# ADC_1_Board.net
KiCad netlist of a schematic drawn in Altium Designer
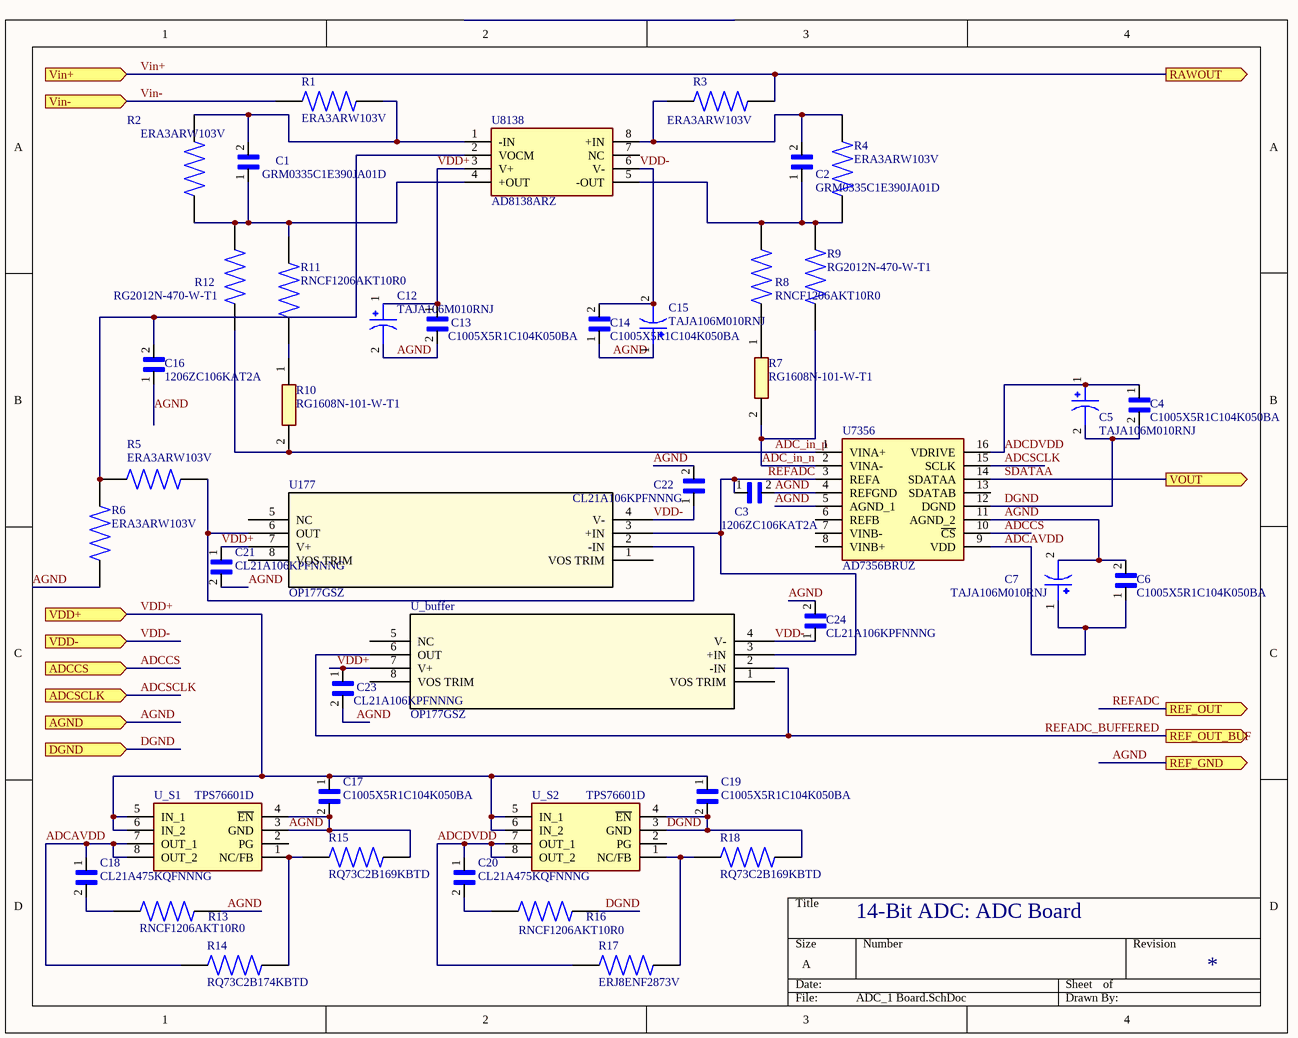
[diagram p0: ADC_1 Board.SchDoc]

(export (version "E")
  (design (tool "Eeschema 10.0.6"))
  (components
    (comp (ref "C1")
      (value "GRM0335C1E390JA01D")
      (footprint "CAPC0603X33N")
      (description "SMD Capacitor C0G(EIA) with Capacitance: 39pF Tol. 5%. Rated Voltage: 25Vdc")
      (libsource (lib "GRM0335C1E390JA01D") (part "GRM0335C1E390JA01D"))
    )
    (comp (ref "C2")
      (value "GRM0335C1E390JA01D")
      (footprint "CAPC0603X33N")
      (description "SMD Capacitor C0G(EIA) with Capacitance: 39pF Tol. 5%. Rated Voltage: 25Vdc")
      (libsource (lib "GRM0335C1E390JA01D") (part "GRM0335C1E390JA01D"))
    )
    (comp (ref "C3")
      (value "1206ZC106KAT2A")
      (footprint "CAPC3216X178N")
      (description "10ÂµF Â±10% 10V Ceramic Capacitor X7R 1206 (3216 Metric)")
      (fields (field (name "MF") "AVX"))
      (libsource (lib "1206ZC106KAT2A") (part "1206ZC106KAT2A"))
    )
    (comp (ref "C4")
      (value "C1005X5R1C104K050BA")
      (footprint "CAPC1005X55N")
      (description "CERAMIC CAPACITOR, 0.1UF, 16V, X5R, 10%, 0402")
      (libsource (lib "") (part "C1005X5R1C104K050BA_1"))
    )
    (comp (ref "C5")
      (value "TAJA106M010RNJ")
      (footprint "CAPMP3216X180N")
      (description "10ÂµF Molded Tantalum Capacitors 10V 1206 (3216 Metric) 3Ohm")
      (fields (field (name "MF") "AVX"))
      (libsource (lib "") (part "TAJA106M010RNJ_1"))
    )
    (comp (ref "C6")
      (value "C1005X5R1C104K050BA")
      (footprint "CAPC1005X55N")
      (description "CERAMIC CAPACITOR, 0.1UF, 16V, X5R, 10%, 0402")
      (libsource (lib "C1005X5R1C104K050BA") (part "C1005X5R1C104K050BA"))
    )
    (comp (ref "C7")
      (value "TAJA106M010RNJ")
      (footprint "CAPMP3216X180N")
      (description "10ÂµF Molded Tantalum Capacitors 10V 1206 (3216 Metric) 3Ohm")
      (fields (field (name "MF") "AVX"))
      (libsource (lib "TAJA106M010RNJ") (part "TAJA106M010RNJ"))
    )
    (comp (ref "C12")
      (value "TAJA106M010RNJ")
      (footprint "CAPMP3216X180N")
      (description "10ÂµF Molded Tantalum Capacitors 10V 1206 (3216 Metric) 3Ohm")
      (fields (field (name "MF") "AVX"))
      (libsource (lib "") (part "TAJA106M010RNJ_1"))
    )
    (comp (ref "C13")
      (value "C1005X5R1C104K050BA")
      (footprint "CAPC1005X55N")
      (description "CERAMIC CAPACITOR, 0.1UF, 16V, X5R, 10%, 0402")
      (libsource (lib "") (part "C1005X5R1C104K050BA_1"))
    )
    (comp (ref "C14")
      (value "C1005X5R1C104K050BA")
      (footprint "CAPC1005X55N")
      (description "CERAMIC CAPACITOR, 0.1UF, 16V, X5R, 10%, 0402")
      (libsource (lib "C1005X5R1C104K050BA") (part "C1005X5R1C104K050BA"))
    )
    (comp (ref "C15")
      (value "TAJA106M010RNJ")
      (footprint "CAPMP3216X180N")
      (description "10ÂµF Molded Tantalum Capacitors 10V 1206 (3216 Metric) 3Ohm")
      (fields (field (name "MF") "AVX"))
      (libsource (lib "TAJA106M010RNJ") (part "TAJA106M010RNJ"))
    )
    (comp (ref "C16")
      (value "1206ZC106KAT2A")
      (footprint "CAPC3216X178N")
      (description "10ÂµF Â±10% 10V Ceramic Capacitor X7R 1206 (3216 Metric)")
      (fields (field (name "MF") "AVX"))
      (libsource (lib "") (part "1206ZC106KAT2A_1"))
    )
    (comp (ref "C17")
      (value "C1005X5R1C104K050BA")
      (footprint "CAPC1005X55N")
      (description "CERAMIC CAPACITOR, 0.1UF, 16V, X5R, 10%, 0402")
      (libsource (lib "") (part "C1005X5R1C104K050BA_1"))
    )
    (comp (ref "C18")
      (value "CL21A475KQFNNNG")
      (footprint "CAPC2012X135N")
      (description "4.7U 6.3V K0805 X5R")
      (libsource (lib "CL21A475KQFNNNG") (part "CL21A475KQFNNNG"))
    )
    (comp (ref "C19")
      (value "C1005X5R1C104K050BA")
      (footprint "CAPC1005X55N")
      (description "CERAMIC CAPACITOR, 0.1UF, 16V, X5R, 10%, 0402")
      (libsource (lib "") (part "C1005X5R1C104K050BA_1"))
    )
    (comp (ref "C20")
      (value "CL21A475KQFNNNG")
      (footprint "CAPC2012X135N")
      (description "4.7U 6.3V K0805 X5R")
      (libsource (lib "CL21A475KQFNNNG") (part "CL21A475KQFNNNG"))
    )
    (comp (ref "C21")
      (value "CL21A106KPFNNNG")
      (footprint "CAPC2012X135N")
      (description "10ÂµF Â±10% 10V Ceramic Capacitor X5R 0805 (2012 Metric)")
      (fields
        (field (name "MF") "Samsung Electro-Mechanics")
        (field (name "DIGI-KEY_PART_NUMBER") "1276-6456-1-ND")
      )
      (libsource (lib "CL21A106KPFNNNG") (part "CL21A106KPFNNNG"))
    )
    (comp (ref "C22")
      (value "CL21A106KPFNNNG")
      (footprint "CAPC2012X135N")
      (description "10ÂµF Â±10% 10V Ceramic Capacitor X5R 0805 (2012 Metric)")
      (fields
        (field (name "MF") "Samsung Electro-Mechanics")
        (field (name "DIGI-KEY_PART_NUMBER") "1276-6456-1-ND")
      )
      (libsource (lib "") (part "CL21A106KPFNNNG_1"))
    )
    (comp (ref "C23")
      (value "CL21A106KPFNNNG")
      (footprint "CAPC2012X135N")
      (description "10ÂµF Â±10% 10V Ceramic Capacitor X5R 0805 (2012 Metric)")
      (fields
        (field (name "MF") "Samsung Electro-Mechanics")
        (field (name "DIGI-KEY_PART_NUMBER") "1276-6456-1-ND")
      )
      (libsource (lib "CL21A106KPFNNNG") (part "CL21A106KPFNNNG"))
    )
    (comp (ref "C24")
      (value "CL21A106KPFNNNG")
      (footprint "CAPC2012X135N")
      (description "10ÂµF Â±10% 10V Ceramic Capacitor X5R 0805 (2012 Metric)")
      (fields
        (field (name "MF") "Samsung Electro-Mechanics")
        (field (name "DIGI-KEY_PART_NUMBER") "1276-6456-1-ND")
      )
      (libsource (lib "") (part "CL21A106KPFNNNG_1"))
    )
    (comp (ref "R1")
      (value "ERA3ARW103V")
      (footprint "RES_ERA3ARW103V")
      (libsource (lib "ERA3ARW103V") (part "ERA3ARW103V"))
    )
    (comp (ref "R2")
      (value "ERA3ARW103V")
      (footprint "RES_ERA3ARW103V")
      (libsource (lib "ERA3ARW103V") (part "ERA3ARW103V"))
    )
    (comp (ref "R3")
      (value "ERA3ARW103V")
      (footprint "RES_ERA3ARW103V")
      (libsource (lib "ERA3ARW103V") (part "ERA3ARW103V"))
    )
    (comp (ref "R4")
      (value "ERA3ARW103V")
      (footprint "RES_ERA3ARW103V")
      (libsource (lib "ERA3ARW103V") (part "ERA3ARW103V"))
    )
    (comp (ref "R5")
      (value "ERA3ARW103V")
      (footprint "RES_ERA3ARW103V")
      (libsource (lib "ERA3ARW103V") (part "ERA3ARW103V"))
    )
    (comp (ref "R6")
      (value "ERA3ARW103V")
      (footprint "RES_ERA3ARW103V")
      (libsource (lib "ERA3ARW103V") (part "ERA3ARW103V"))
    )
    (comp (ref "R7")
      (value "RG1608N-101-W-T1")
      (footprint "SamacSys:RESC1608X50N")
      (description "Resistor")
      (libsource (lib "*") (part "RG1608N-101-W-T1"))
    )
    (comp (ref "R8")
      (value "RNCF1206AKT10R0")
      (footprint "RESC3015X65N")
      (libsource (lib "RNCF1206AKT10R0") (part "RNCF1206AKT10R0"))
    )
    (comp (ref "R9")
      (value "RG2012N-470-W-T1")
      (footprint "RESC2012X50N")
      (libsource (lib "RG2012N-470-W-T1") (part "RG2012N-470-W-T1"))
    )
    (comp (ref "R10")
      (value "RG1608N-101-W-T1")
      (footprint "SamacSys:RESC1608X50N")
      (description "Resistor")
      (libsource (lib "*") (part "RG1608N-101-W-T1"))
    )
    (comp (ref "R11")
      (value "RNCF1206AKT10R0")
      (footprint "RESC3015X65N")
      (libsource (lib "RNCF1206AKT10R0") (part "RNCF1206AKT10R0"))
    )
    (comp (ref "R12")
      (value "RG2012N-470-W-T1")
      (footprint "RESC2012X50N")
      (libsource (lib "RG2012N-470-W-T1") (part "RG2012N-470-W-T1"))
    )
    (comp (ref "R13")
      (value "RNCF1206AKT10R0")
      (footprint "RESC3015X65N")
      (libsource (lib "RNCF1206AKT10R0") (part "RNCF1206AKT10R0"))
    )
    (comp (ref "R14")
      (value "RQ73C2B174KBTD")
      (footprint "RESC3116X75N")
      (libsource (lib "RQ73C2B174KBTD") (part "RQ73C2B174KBTD"))
    )
    (comp (ref "R15")
      (value "RQ73C2B169KBTD")
      (footprint "RESC3116X75N")
      (libsource (lib "RQ73C2B169KBTD") (part "RQ73C2B169KBTD"))
    )
    (comp (ref "R16")
      (value "RNCF1206AKT10R0")
      (footprint "RESC3015X65N")
      (libsource (lib "RNCF1206AKT10R0") (part "RNCF1206AKT10R0"))
    )
    (comp (ref "R17")
      (value "ERJ8ENF2873V")
      (footprint "RES_ERJ8ENF2873V")
      (libsource (lib "ERJ8ENF2873V") (part "ERJ8ENF2873V"))
    )
    (comp (ref "R18")
      (value "RQ73C2B169KBTD")
      (footprint "RESC3116X75N")
      (libsource (lib "RQ73C2B169KBTD") (part "RQ73C2B169KBTD"))
    )
    (comp (ref "U177")
      (value "OP177GSZ")
      (footprint "R_8_ADI")
      (description "No Description Available")
      (fields (field (name "COPYRIGHT") "Copyright (C) 2021 Accelerated Designs. All rights reserved"))
      (libsource (lib "OP177GSZ") (part "OP177GSZ"))
    )
    (comp (ref "U7356")
      (value "AD7356BRUZ")
      (footprint "SamacSys:SOP65P640X120-16N")
      (description "Integrated Circuit")
      (libsource (lib "*") (part "AD7356BRUZ"))
    )
    (comp (ref "U8138")
      (value "AD8138ARZ")
      (footprint "SamacSys:SOIC127P600X175-8N")
      (description "Integrated Circuit")
      (fields (field (name "MOUSER2 PART NUMBER") "584-AD8138ARZ"))
      (libsource (lib "*") (part "AD8138ARZ"))
    )
    (comp (ref "U_buffer")
      (value "OP177GSZ")
      (footprint "R_8_ADI")
      (description "No Description Available")
      (fields (field (name "COPYRIGHT") "Copyright (C) 2021 Accelerated Designs. All rights reserved"))
      (libsource (lib "OP177GSZ") (part "OP177GSZ"))
    )
    (comp (ref "U_S1")
      (value "TPS76601D")
      (footprint "SamacSys:SOIC127P600X175-8N")
      (description "Integrated Circuit")
      (libsource (lib "*") (part "TPS76601D"))
    )
    (comp (ref "U_S2")
      (value "TPS76601D")
      (footprint "SamacSys:SOIC127P600X175-8N")
      (description "Integrated Circuit")
      (libsource (lib "*") (part "TPS76601D"))
    )
  )
  (nets
    (net (code "1") (name "/ADCAVDD") (class "Default")
      (node (ref "C18") (pin "1") (pinfunction "1_1") (pintype "passive"))
      (node (ref "C6") (pin "1") (pinfunction "1_1") (pintype "passive"))
      (node (ref "C7") (pin "1") (pinfunction "1_1") (pintype "passive"))
      (node (ref "R14") (pin "1") (pinfunction "1_1") (pintype "passive"))
      (node (ref "U7356") (pin "9") (pinfunction "VDD_9") (pintype "passive"))
      (node (ref "U_S1") (pin "7") (pinfunction "OUT_1_7") (pintype "passive"))
      (node (ref "U_S1") (pin "8") (pinfunction "OUT_2_8") (pintype "passive"))
    )
    (net (code "2") (name "/ADCCS") (class "Default")
      (node (ref "U7356") (pin "10") (pinfunction "~{CS}_10") (pintype "passive"))
    )
    (net (code "3") (name "/ADCDVDD") (class "Default")
      (node (ref "C20") (pin "1") (pinfunction "1_1") (pintype "passive"))
      (node (ref "C4") (pin "1") (pinfunction "1_1") (pintype "passive"))
      (node (ref "C5") (pin "1") (pinfunction "1_1") (pintype "passive"))
      (node (ref "R17") (pin "1") (pinfunction "1_1") (pintype "passive"))
      (node (ref "U7356") (pin "16") (pinfunction "VDRIVE_16") (pintype "passive"))
      (node (ref "U_S2") (pin "7") (pinfunction "OUT_1_7") (pintype "passive"))
      (node (ref "U_S2") (pin "8") (pinfunction "OUT_2_8") (pintype "passive"))
    )
    (net (code "4") (name "/ADCSCLK") (class "Default")
      (node (ref "U7356") (pin "15") (pinfunction "SCLK_15") (pintype "passive"))
    )
    (net (code "5") (name "/ADC_in_n") (class "Default")
      (node (ref "R7") (pin "2") (pinfunction "2_2") (pintype "passive"))
      (node (ref "R9") (pin "2") (pinfunction "2_2") (pintype "passive"))
      (node (ref "U7356") (pin "2") (pinfunction "VINA-_2") (pintype "passive"))
    )
    (net (code "6") (name "/ADC_in_p") (class "Default")
      (node (ref "R10") (pin "2") (pinfunction "2_2") (pintype "passive"))
      (node (ref "R12") (pin "2") (pinfunction "2_2") (pintype "passive"))
      (node (ref "U7356") (pin "1") (pinfunction "VINA+_1") (pintype "passive"))
    )
    (net (code "7") (name "/AGND") (class "Default")
      (node (ref "C12") (pin "2") (pinfunction "2_2") (pintype "passive"))
      (node (ref "C13") (pin "2") (pinfunction "2_2") (pintype "passive"))
      (node (ref "C14") (pin "1") (pinfunction "1_1") (pintype "passive"))
      (node (ref "C15") (pin "1") (pinfunction "1_1") (pintype "passive"))
      (node (ref "C16") (pin "1") (pinfunction "1_1") (pintype "passive"))
      (node (ref "C17") (pin "2") (pinfunction "2_2") (pintype "passive"))
      (node (ref "C21") (pin "2") (pinfunction "2_2") (pintype "passive"))
      (node (ref "C22") (pin "2") (pinfunction "2_2") (pintype "passive"))
      (node (ref "C23") (pin "2") (pinfunction "2_2") (pintype "passive"))
      (node (ref "C24") (pin "2") (pinfunction "2_2") (pintype "passive"))
      (node (ref "C3") (pin "2") (pinfunction "2_2") (pintype "passive"))
      (node (ref "C6") (pin "2") (pinfunction "2_2") (pintype "passive"))
      (node (ref "C7") (pin "2") (pinfunction "2_2") (pintype "passive"))
      (node (ref "R13") (pin "1") (pinfunction "1_1") (pintype "passive"))
      (node (ref "R15") (pin "2") (pinfunction "2_2") (pintype "passive"))
      (node (ref "R6") (pin "2") (pinfunction "2_2") (pintype "passive"))
      (node (ref "U7356") (pin "11") (pinfunction "AGND_2_11") (pintype "passive"))
      (node (ref "U7356") (pin "4") (pinfunction "REFGND_4") (pintype "passive"))
      (node (ref "U7356") (pin "5") (pinfunction "AGND_1_5") (pintype "passive"))
      (node (ref "U_S1") (pin "3") (pinfunction "GND_3") (pintype "passive"))
      (node (ref "U_S1") (pin "4") (pinfunction "~{EN}_4") (pintype "passive"))
    )
    (net (code "8") (name "/DGND") (class "Default")
      (node (ref "C19") (pin "2") (pinfunction "2_2") (pintype "passive"))
      (node (ref "C4") (pin "2") (pinfunction "2_2") (pintype "passive"))
      (node (ref "C5") (pin "2") (pinfunction "2_2") (pintype "passive"))
      (node (ref "R16") (pin "1") (pinfunction "1_1") (pintype "passive"))
      (node (ref "R18") (pin "2") (pinfunction "2_2") (pintype "passive"))
      (node (ref "U7356") (pin "12") (pinfunction "DGND_12") (pintype "passive"))
      (node (ref "U_S2") (pin "3") (pinfunction "GND_3") (pintype "passive"))
      (node (ref "U_S2") (pin "4") (pinfunction "~{EN}_4") (pintype "passive"))
    )
    (net (code "9") (name "/REFADC") (class "Default")
      (node (ref "C3") (pin "1") (pinfunction "1_1") (pintype "passive"))
      (node (ref "U177") (pin "3") (pinfunction "+IN_3") (pintype "passive"))
      (node (ref "U7356") (pin "3") (pinfunction "REFA_3") (pintype "passive"))
      (node (ref "U_buffer") (pin "3") (pinfunction "+IN_3") (pintype "passive"))
    )
    (net (code "10") (name "/REFADC_BUFFERED") (class "Default")
      (node (ref "U_buffer") (pin "2") (pinfunction "-IN_2") (pintype "passive"))
      (node (ref "U_buffer") (pin "6") (pinfunction "OUT_6") (pintype "passive"))
    )
    (net (code "11") (name "/SDATAA") (class "Default")
      (node (ref "U7356") (pin "14") (pinfunction "SDATAA_14") (pintype "passive"))
    )
    (net (code "12") (name "/VDD+") (class "Default")
      (node (ref "C12") (pin "1") (pinfunction "1_1") (pintype "passive"))
      (node (ref "C13") (pin "1") (pinfunction "1_1") (pintype "passive"))
      (node (ref "C17") (pin "1") (pinfunction "1_1") (pintype "passive"))
      (node (ref "C19") (pin "1") (pinfunction "1_1") (pintype "passive"))
      (node (ref "C21") (pin "1") (pinfunction "1_1") (pintype "passive"))
      (node (ref "C23") (pin "1") (pinfunction "1_1") (pintype "passive"))
      (node (ref "U177") (pin "7") (pinfunction "V+_7") (pintype "power_in"))
      (node (ref "U8138") (pin "3") (pinfunction "V+_3") (pintype "passive"))
      (node (ref "U_S1") (pin "5") (pinfunction "IN_1_5") (pintype "passive"))
      (node (ref "U_S1") (pin "6") (pinfunction "IN_2_6") (pintype "passive"))
      (node (ref "U_S2") (pin "5") (pinfunction "IN_1_5") (pintype "passive"))
      (node (ref "U_S2") (pin "6") (pinfunction "IN_2_6") (pintype "passive"))
      (node (ref "U_buffer") (pin "7") (pinfunction "V+_7") (pintype "power_in"))
    )
    (net (code "13") (name "/VDD-") (class "Default")
      (node (ref "C14") (pin "2") (pinfunction "2_2") (pintype "passive"))
      (node (ref "C15") (pin "2") (pinfunction "2_2") (pintype "passive"))
      (node (ref "C22") (pin "1") (pinfunction "1_1") (pintype "passive"))
      (node (ref "C24") (pin "1") (pinfunction "1_1") (pintype "passive"))
      (node (ref "U177") (pin "4") (pinfunction "V-_4") (pintype "power_in"))
      (node (ref "U8138") (pin "6") (pinfunction "V-_6") (pintype "passive"))
      (node (ref "U_buffer") (pin "4") (pinfunction "V-_4") (pintype "power_in"))
    )
    (net (code "14") (name "/Vin+") (class "Default")
      (node (ref "R3") (pin "1") (pinfunction "1_1") (pintype "passive"))
    )
    (net (code "15") (name "/Vin-") (class "Default")
      (node (ref "R1") (pin "2") (pinfunction "2_2") (pintype "passive"))
    )
    (net (code "16") (name "Net-(C18-Pad2)") (class "Default")
      (node (ref "C18") (pin "2") (pinfunction "2_2") (pintype "passive"))
      (node (ref "R13") (pin "2") (pinfunction "2_2") (pintype "passive"))
    )
    (net (code "17") (name "Net-(C20-Pad2)") (class "Default")
      (node (ref "C20") (pin "2") (pinfunction "2_2") (pintype "passive"))
      (node (ref "R16") (pin "2") (pinfunction "2_2") (pintype "passive"))
    )
    (net (code "18") (name "Net-(R7-Pad1)") (class "Default")
      (node (ref "R7") (pin "1") (pinfunction "1_1") (pintype "passive"))
      (node (ref "R8") (pin "1") (pinfunction "1_1") (pintype "passive"))
    )
    (net (code "19") (name "Net-(R10-Pad1)") (class "Default")
      (node (ref "R10") (pin "1") (pinfunction "1_1") (pintype "passive"))
      (node (ref "R11") (pin "2") (pinfunction "2_2") (pintype "passive"))
    )
    (net (code "20") (name "Net-(U177--IN)") (class "Default")
      (node (ref "R5") (pin "2") (pinfunction "2_2") (pintype "passive"))
      (node (ref "U177") (pin "2") (pinfunction "-IN_2") (pintype "passive"))
      (node (ref "U177") (pin "6") (pinfunction "OUT_6") (pintype "passive"))
    )
    (net (code "21") (name "Net-(U8138-+IN)") (class "Default")
      (node (ref "C2") (pin "2") (pinfunction "2_2") (pintype "passive"))
      (node (ref "R3") (pin "2") (pinfunction "2_2") (pintype "passive"))
      (node (ref "R4") (pin "1") (pinfunction "1_1") (pintype "passive"))
      (node (ref "U8138") (pin "8") (pinfunction "+IN_8") (pintype "passive"))
    )
    (net (code "22") (name "Net-(U8138-+OUT)") (class "Default")
      (node (ref "C1") (pin "1") (pinfunction "1_1") (pintype "passive"))
      (node (ref "R11") (pin "1") (pinfunction "1_1") (pintype "passive"))
      (node (ref "R12") (pin "1") (pinfunction "1_1") (pintype "passive"))
      (node (ref "R2") (pin "2") (pinfunction "2_2") (pintype "passive"))
      (node (ref "U8138") (pin "4") (pinfunction "+OUT_4") (pintype "passive"))
    )
    (net (code "23") (name "Net-(U8138--IN)") (class "Default")
      (node (ref "C1") (pin "2") (pinfunction "2_2") (pintype "passive"))
      (node (ref "R1") (pin "1") (pinfunction "1_1") (pintype "passive"))
      (node (ref "R2") (pin "1") (pinfunction "1_1") (pintype "passive"))
      (node (ref "U8138") (pin "1") (pinfunction "-IN_1") (pintype "passive"))
    )
    (net (code "24") (name "Net-(U8138--OUT)") (class "Default")
      (node (ref "C2") (pin "1") (pinfunction "1_1") (pintype "passive"))
      (node (ref "R4") (pin "2") (pinfunction "2_2") (pintype "passive"))
      (node (ref "R8") (pin "2") (pinfunction "2_2") (pintype "passive"))
      (node (ref "R9") (pin "1") (pinfunction "1_1") (pintype "passive"))
      (node (ref "U8138") (pin "5") (pinfunction "-OUT_5") (pintype "passive"))
    )
    (net (code "25") (name "Net-(U8138-VOCM)") (class "Default")
      (node (ref "C16") (pin "2") (pinfunction "2_2") (pintype "passive"))
      (node (ref "R5") (pin "1") (pinfunction "1_1") (pintype "passive"))
      (node (ref "R6") (pin "1") (pinfunction "1_1") (pintype "passive"))
      (node (ref "U8138") (pin "2") (pinfunction "VOCM_2") (pintype "passive"))
    )
    (net (code "26") (name "Net-(U_S1-NC{slash}FB)") (class "Default")
      (node (ref "R14") (pin "2") (pinfunction "2_2") (pintype "passive"))
      (node (ref "R15") (pin "1") (pinfunction "1_1") (pintype "passive"))
      (node (ref "U_S1") (pin "1") (pinfunction "NC/FB_1") (pintype "passive"))
    )
    (net (code "27") (name "Net-(U_S2-NC{slash}FB)") (class "Default")
      (node (ref "R17") (pin "2") (pinfunction "2_2") (pintype "passive"))
      (node (ref "R18") (pin "1") (pinfunction "1_1") (pintype "passive"))
      (node (ref "U_S2") (pin "1") (pinfunction "NC/FB_1") (pintype "passive"))
    )
    (net (code "28") (name "unconnected-(U177-NC-Pad5)") (class "Default")
      (node (ref "U177") (pin "5") (pinfunction "NC_5") (pintype "passive"))
    )
    (net (code "29") (name "unconnected-(U177-VOS_TRIM-Pad1)") (class "Default")
      (node (ref "U177") (pin "1") (pinfunction "VOS_TRIM_1") (pintype "passive"))
    )
    (net (code "30") (name "unconnected-(U177-VOS_TRIM-Pad8)") (class "Default")
      (node (ref "U177") (pin "8") (pinfunction "VOS_TRIM_8") (pintype "power_in"))
    )
    (net (code "31") (name "unconnected-(U7356-REFB-Pad6)") (class "Default")
      (node (ref "U7356") (pin "6") (pinfunction "REFB_6") (pintype "passive"))
    )
    (net (code "32") (name "unconnected-(U7356-SDATAB-Pad13)") (class "Default")
      (node (ref "U7356") (pin "13") (pinfunction "SDATAB_13") (pintype "passive"))
    )
    (net (code "33") (name "unconnected-(U7356-VINB+-Pad8)") (class "Default")
      (node (ref "U7356") (pin "8") (pinfunction "VINB+_8") (pintype "passive"))
    )
    (net (code "34") (name "unconnected-(U7356-VINB--Pad7)") (class "Default")
      (node (ref "U7356") (pin "7") (pinfunction "VINB-_7") (pintype "passive"))
    )
    (net (code "35") (name "unconnected-(U8138-NC-Pad7)") (class "Default")
      (node (ref "U8138") (pin "7") (pinfunction "NC_7") (pintype "passive"))
    )
    (net (code "36") (name "unconnected-(U_S1-PG-Pad2)") (class "Default")
      (node (ref "U_S1") (pin "2") (pinfunction "PG_2") (pintype "passive"))
    )
    (net (code "37") (name "unconnected-(U_S2-PG-Pad2)") (class "Default")
      (node (ref "U_S2") (pin "2") (pinfunction "PG_2") (pintype "passive"))
    )
    (net (code "38") (name "unconnected-(U_buffer-NC-Pad5)") (class "Default")
      (node (ref "U_buffer") (pin "5") (pinfunction "NC_5") (pintype "passive"))
    )
    (net (code "39") (name "unconnected-(U_buffer-VOS_TRIM-Pad1)") (class "Default")
      (node (ref "U_buffer") (pin "1") (pinfunction "VOS_TRIM_1") (pintype "passive"))
    )
    (net (code "40") (name "unconnected-(U_buffer-VOS_TRIM-Pad8)") (class "Default")
      (node (ref "U_buffer") (pin "8") (pinfunction "VOS_TRIM_8") (pintype "power_in"))
    )
  )
)
